# main.net
KiCad netlist of a schematic drawn in EAGLE
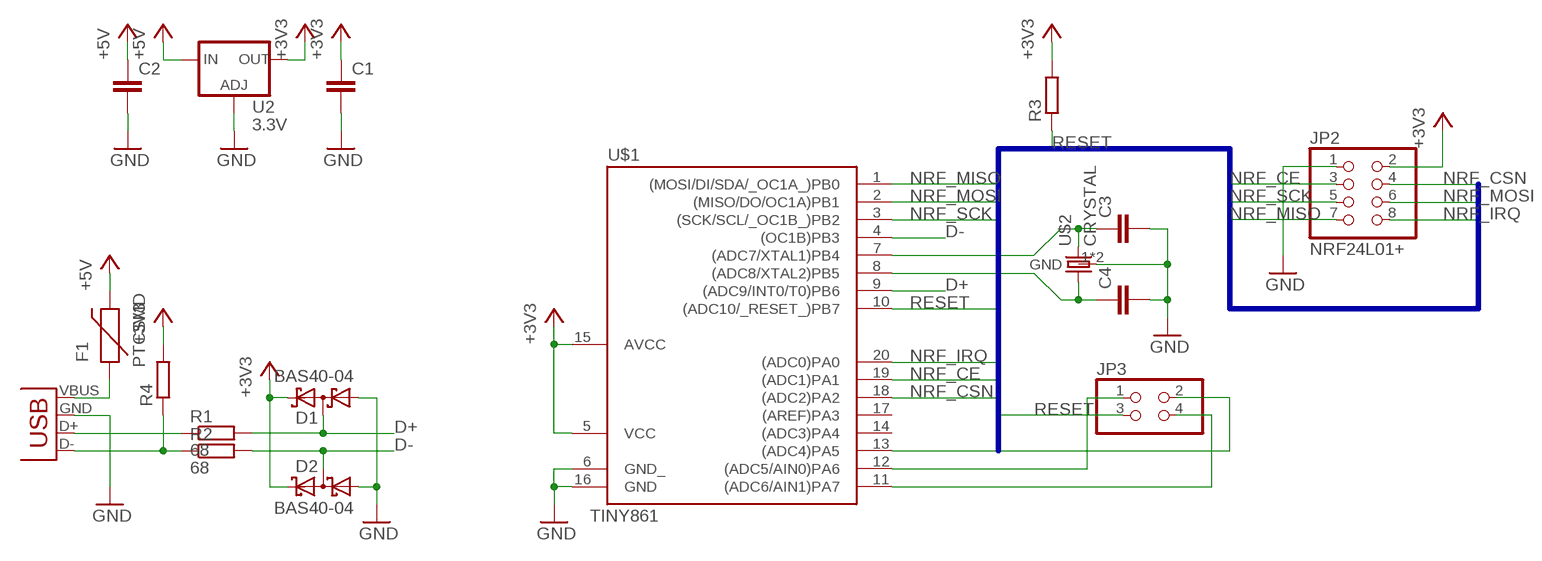
[diagram p0: schematic, sheet 1]

(export (version "E")
  (design (tool "Eeschema 10.0.6"))
  (components
    (comp (ref "C1")
      (value "C-EUC1206")
      (footprint "eagle-import:C1206")
      (libsource (lib "eagle-import") (part "C-EUC1206"))
    )
    (comp (ref "C2")
      (value "C-EUC1206")
      (footprint "eagle-import:C1206")
      (libsource (lib "eagle-import") (part "C-EUC1206"))
    )
    (comp (ref "C3")
      (value "C-EUC0805")
      (footprint "eagle-import:C0805")
      (libsource (lib "eagle-import") (part "C-EUC0805"))
    )
    (comp (ref "C4")
      (value "C-EUC0805")
      (footprint "eagle-import:C0805")
      (libsource (lib "eagle-import") (part "C-EUC0805"))
    )
    (comp (ref "D1")
      (value "BAS40-04")
      (footprint "eagle-import:SOT23")
      (libsource (lib "eagle-import") (part "BAS40-04"))
    )
    (comp (ref "D2")
      (value "BAS40-04")
      (footprint "eagle-import:SOT23")
      (libsource (lib "eagle-import") (part "BAS40-04"))
    )
    (comp (ref "F1")
      (value "PTCSMD")
      (footprint "eagle-import:PTC-1206")
      (libsource (lib "eagle-import") (part "PTCSMD"))
    )
    (comp (ref "JP1")
      (value "USB-A-H")
      (footprint "eagle-import:USB-A-H")
      (libsource (lib "eagle-import") (part "USB-A-H"))
    )
    (comp (ref "JP2")
      (value "NRF24L01+")
      (footprint "eagle-import:2X04")
      (libsource (lib "eagle-import") (part "PINHD-2X4"))
    )
    (comp (ref "JP3")
      (value "PINHD-2X2")
      (footprint "eagle-import:2X02")
      (libsource (lib "eagle-import") (part "PINHD-2X2"))
    )
    (comp (ref "R1")
      (value "68")
      (footprint "eagle-import:R1206")
      (libsource (lib "eagle-import") (part "R-EU_R1206"))
    )
    (comp (ref "R2")
      (value "68")
      (footprint "eagle-import:R1206")
      (libsource (lib "eagle-import") (part "R-EU_R1206"))
    )
    (comp (ref "R3")
      (value "R-EU_R1206")
      (footprint "eagle-import:R1206")
      (libsource (lib "eagle-import") (part "R-EU_R1206"))
    )
    (comp (ref "R4")
      (value "R-EU_R1206")
      (footprint "eagle-import:R1206")
      (libsource (lib "eagle-import") (part "R-EU_R1206"))
    )
    (comp (ref "U$1")
      (value "TINY861")
      (footprint "eagle-import:SO20L$")
      (libsource (lib "eagle-import") (part "TINY26S"))
    )
    (comp (ref "U$2")
      (value "CRYSTAL")
      (footprint "eagle-import:5X7")
      (libsource (lib "eagle-import") (part "CRYSTAL"))
    )
    (comp (ref "U2")
      (value "3.3V")
      (footprint "eagle-import:SOT223")
      (libsource (lib "eagle-import") (part "V_REG_317SMD"))
    )
  )
  (nets
    (net (code "1") (name "+3V3") (class "Default")
      (node (ref "C1") (pin "1") (pinfunction "1_1") (pintype "passive"))
      (node (ref "D1") (pin "2") (pinfunction "C2_2") (pintype "passive"))
      (node (ref "D2") (pin "2") (pinfunction "C2_2") (pintype "passive"))
      (node (ref "JP2") (pin "2") (pinfunction "2_2") (pintype "passive"))
      (node (ref "R3") (pin "2") (pinfunction "2_2") (pintype "passive"))
      (node (ref "R4") (pin "2") (pinfunction "2_2") (pintype "passive"))
      (node (ref "U$1") (pin "15") (pinfunction "AVCC_15") (pintype "power_in"))
      (node (ref "U$1") (pin "5") (pinfunction "VCC_5") (pintype "power_in"))
      (node (ref "U2") (pin "2") (pinfunction "OUT_2") (pintype "output"))
    )
    (net (code "2") (name "+5V") (class "Default")
      (node (ref "C2") (pin "1") (pinfunction "1_1") (pintype "passive"))
      (node (ref "F1") (pin "2") (pinfunction "2_2") (pintype "bidirectional"))
      (node (ref "U2") (pin "3") (pinfunction "IN_3") (pintype "input"))
    )
    (net (code "3") (name "/D+") (class "Default")
      (node (ref "D1") (pin "3") (pinfunction "C1A2_3") (pintype "passive"))
      (node (ref "R1") (pin "2") (pinfunction "2_2") (pintype "passive"))
      (node (ref "U$1") (pin "9") (pinfunction "(ADC9/INT0/T0)PB6_9") (pintype "bidirectional"))
    )
    (net (code "4") (name "/D-") (class "Default")
      (node (ref "D2") (pin "3") (pinfunction "C1A2_3") (pintype "passive"))
      (node (ref "R2") (pin "2") (pinfunction "2_2") (pintype "passive"))
      (node (ref "U$1") (pin "4") (pinfunction "(OC1B)PB3_4") (pintype "bidirectional"))
    )
    (net (code "5") (name "/NRF_CE") (class "Default")
      (node (ref "JP2") (pin "3") (pinfunction "3_3") (pintype "passive"))
      (node (ref "U$1") (pin "19") (pinfunction "(ADC1)PA1_19") (pintype "bidirectional"))
    )
    (net (code "6") (name "/NRF_CSN") (class "Default")
      (node (ref "JP2") (pin "4") (pinfunction "4_4") (pintype "passive"))
      (node (ref "U$1") (pin "18") (pinfunction "(ADC2)PA2_18") (pintype "bidirectional"))
    )
    (net (code "7") (name "/NRF_IRQ") (class "Default")
      (node (ref "JP2") (pin "8") (pinfunction "8_8") (pintype "passive"))
      (node (ref "U$1") (pin "20") (pinfunction "(ADC0)PA0_20") (pintype "bidirectional"))
    )
    (net (code "8") (name "/NRF_MISO") (class "Default")
      (node (ref "JP2") (pin "7") (pinfunction "7_7") (pintype "passive"))
      (node (ref "U$1") (pin "1") (pinfunction "(MOSI/DI/SDA/_OC1A_)PB0_1") (pintype "bidirectional"))
    )
    (net (code "9") (name "/NRF_MOSI") (class "Default")
      (node (ref "JP2") (pin "6") (pinfunction "6_6") (pintype "passive"))
      (node (ref "U$1") (pin "2") (pinfunction "(MISO/DO/OC1A)PB1_2") (pintype "bidirectional"))
    )
    (net (code "10") (name "/NRF_SCK") (class "Default")
      (node (ref "JP2") (pin "5") (pinfunction "5_5") (pintype "passive"))
      (node (ref "U$1") (pin "3") (pinfunction "(SCK/SCL/_OC1B_)PB2_3") (pintype "bidirectional"))
    )
    (net (code "11") (name "/RESET") (class "Default")
      (node (ref "JP3") (pin "3") (pinfunction "3_3") (pintype "passive"))
      (node (ref "R3") (pin "1") (pinfunction "1_1") (pintype "passive"))
      (node (ref "U$1") (pin "10") (pinfunction "(ADC10/_RESET_)PB7_10") (pintype "bidirectional"))
    )
    (net (code "12") (name "GND") (class "Default")
      (node (ref "C1") (pin "2") (pinfunction "2_2") (pintype "passive"))
      (node (ref "C2") (pin "2") (pinfunction "2_2") (pintype "passive"))
      (node (ref "C3") (pin "2") (pinfunction "2_2") (pintype "passive"))
      (node (ref "C4") (pin "2") (pinfunction "2_2") (pintype "passive"))
      (node (ref "D1") (pin "1") (pinfunction "A1_1") (pintype "passive"))
      (node (ref "D2") (pin "1") (pinfunction "A1_1") (pintype "passive"))
      (node (ref "JP1") (pin "GND") (pinfunction "VBUS_GND") (pintype "bidirectional"))
      (node (ref "JP2") (pin "1") (pinfunction "1_1") (pintype "passive"))
      (node (ref "U$1") (pin "16") (pinfunction "GND_16") (pintype "power_in"))
      (node (ref "U$1") (pin "6") (pinfunction "GND__6") (pintype "power_in"))
      (node (ref "U$2") (pin "1") (pinfunction "GND_1") (pintype "bidirectional"))
      (node (ref "U$2") (pin "3") (pinfunction "GND_3") (pintype "bidirectional"))
      (node (ref "U2") (pin "1") (pinfunction "ADJ_1") (pintype "input"))
    )
    (net (code "13") (name "Net-(JP1-D+)") (class "Default")
      (node (ref "JP1") (pin "D-") (pinfunction "D+_D-") (pintype "bidirectional"))
      (node (ref "R2") (pin "1") (pinfunction "1_1") (pintype "passive"))
      (node (ref "R4") (pin "1") (pinfunction "1_1") (pintype "passive"))
    )
    (net (code "14") (name "Net-(JP1-D-)") (class "Default")
      (node (ref "JP1") (pin "D+") (pinfunction "D-_D+") (pintype "bidirectional"))
      (node (ref "R1") (pin "1") (pinfunction "1_1") (pintype "passive"))
    )
    (net (code "15") (name "Net-(JP1-GND)") (class "Default")
      (node (ref "F1") (pin "1") (pinfunction "1_1") (pintype "bidirectional"))
      (node (ref "JP1") (pin "VBUS") (pinfunction "GND_VBUS") (pintype "bidirectional"))
    )
    (net (code "16") (name "Net-(U$1-(ADC4)PA5)") (class "Default")
      (node (ref "JP3") (pin "2") (pinfunction "2_2") (pintype "passive"))
      (node (ref "U$1") (pin "13") (pinfunction "(ADC4)PA5_13") (pintype "bidirectional"))
    )
    (net (code "17") (name "Net-(U$1-(ADC5{slash}AIN0)PA6)") (class "Default")
      (node (ref "JP3") (pin "1") (pinfunction "1_1") (pintype "passive"))
      (node (ref "U$1") (pin "12") (pinfunction "(ADC5/AIN0)PA6_12") (pintype "bidirectional"))
    )
    (net (code "18") (name "Net-(U$1-(ADC6{slash}AIN1)PA7)") (class "Default")
      (node (ref "JP3") (pin "4") (pinfunction "4_4") (pintype "passive"))
      (node (ref "U$1") (pin "11") (pinfunction "(ADC6/AIN1)PA7_11") (pintype "bidirectional"))
    )
    (net (code "19") (name "Net-(U$1-(ADC7{slash}XTAL1)PB4)") (class "Default")
      (node (ref "C3") (pin "1") (pinfunction "1_1") (pintype "passive"))
      (node (ref "U$1") (pin "7") (pinfunction "(ADC7/XTAL1)PB4_7") (pintype "bidirectional"))
      (node (ref "U$2") (pin "4") (pinfunction "2_4") (pintype "passive"))
    )
    (net (code "20") (name "Net-(U$1-(ADC8{slash}XTAL2)PB5)") (class "Default")
      (node (ref "C4") (pin "1") (pinfunction "1_1") (pintype "passive"))
      (node (ref "U$1") (pin "8") (pinfunction "(ADC8/XTAL2)PB5_8") (pintype "bidirectional"))
      (node (ref "U$2") (pin "2") (pinfunction "1_2") (pintype "passive"))
    )
    (net (code "21") (name "unconnected-(U$1-(ADC3)PA4-Pad14)") (class "Default")
      (node (ref "U$1") (pin "14") (pinfunction "(ADC3)PA4_14") (pintype "bidirectional"))
    )
    (net (code "22") (name "unconnected-(U$1-(AREF)PA3-Pad17)") (class "Default")
      (node (ref "U$1") (pin "17") (pinfunction "(AREF)PA3_17") (pintype "bidirectional"))
    )
  )
)
